# ActiveHeadphone2.net
KiCad netlist of a schematic drawn in EAGLE
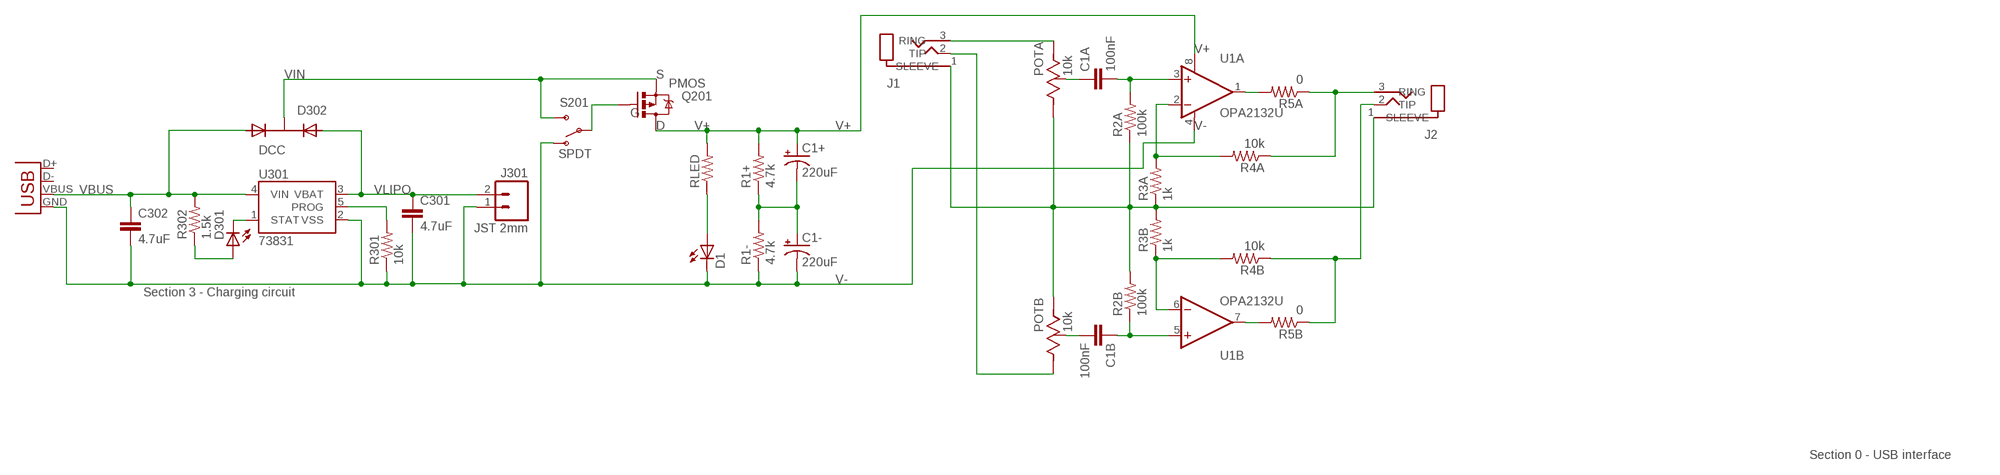
[diagram p0: schematic, sheet 1]

(export (version "E")
  (design (tool "Eeschema 10.0.6"))
  (components
    (comp (ref "C1+")
      (value "220uF")
      (footprint "eagle-import:EIA7343")
      (libsource (lib "eagle-import") (part "CAP_POL7343"))
    )
    (comp (ref "C1-")
      (value "220uF")
      (footprint "eagle-import:EIA7343")
      (libsource (lib "eagle-import") (part "CAP_POL7343"))
    )
    (comp (ref "C1A")
      (value "100nF")
      (footprint "eagle-import:0603-CAP")
      (libsource (lib "eagle-import") (part "CAP0603-CAP"))
    )
    (comp (ref "C1B")
      (value "100nF")
      (footprint "eagle-import:0603-CAP")
      (libsource (lib "eagle-import") (part "CAP0603-CAP"))
    )
    (comp (ref "C301")
      (value "4.7uF")
      (footprint "eagle-import:0603-CAP")
      (libsource (lib "eagle-import") (part "CAP0603-CAP"))
    )
    (comp (ref "C302")
      (value "4.7uF")
      (footprint "eagle-import:0603-CAP")
      (libsource (lib "eagle-import") (part "CAP0603-CAP"))
    )
    (comp (ref "D1")
      (value "RED")
      (footprint "eagle-import:LED-0603")
      (libsource (lib "eagle-import") (part "LED0603"))
    )
    (comp (ref "D301")
      (value "RED")
      (footprint "eagle-import:LED-0603")
      (libsource (lib "eagle-import") (part "LED0603"))
    )
    (comp (ref "D302")
      (value "DCC")
      (footprint "eagle-import:SOT-23-3")
      (libsource (lib "eagle-import") (part "PMEG2005CT"))
    )
    (comp (ref "J1")
      (value "3.5mm")
      (footprint "eagle-import:SJ1-3513-SMT")
      (libsource (lib "eagle-import") (part "SJ1-3513-SMT"))
    )
    (comp (ref "J2")
      (value "3.5mm")
      (footprint "eagle-import:SJ1-3513-SMT")
      (libsource (lib "eagle-import") (part "SJ1-3513-SMT"))
    )
    (comp (ref "J003")
      (value "USBSMD")
      (footprint "eagle-import:USB-MINIB")
      (libsource (lib "eagle-import") (part "USBSMD"))
    )
    (comp (ref "J301")
      (value "JST 2mm")
      (footprint "eagle-import:JST-2-SMD")
      (libsource (lib "eagle-import") (part "M02-JST-2MM-SMT"))
    )
    (comp (ref "POTA")
      (value "10k")
      (footprint "eagle-import:3352T")
      (libsource (lib "eagle-import") (part "3352T"))
    )
    (comp (ref "POTB")
      (value "10k")
      (footprint "eagle-import:3352T")
      (libsource (lib "eagle-import") (part "3352T"))
    )
    (comp (ref "Q201")
      (value "PMOS")
      (footprint "eagle-import:SOT23-3")
      (libsource (lib "eagle-import") (part "MOSFET-PCHANNELSMD"))
    )
    (comp (ref "R1+")
      (value "4.7k")
      (footprint "eagle-import:0603-RES")
      (libsource (lib "eagle-import") (part "RESISTOR0603-RES"))
    )
    (comp (ref "R1-")
      (value "4.7k")
      (footprint "eagle-import:0603-RES")
      (libsource (lib "eagle-import") (part "RESISTOR0603-RES"))
    )
    (comp (ref "R2A")
      (value "100k")
      (footprint "eagle-import:0603-RES")
      (libsource (lib "eagle-import") (part "RESISTOR0603-RES"))
    )
    (comp (ref "R2B")
      (value "100k")
      (footprint "eagle-import:0603-RES")
      (libsource (lib "eagle-import") (part "RESISTOR0603-RES"))
    )
    (comp (ref "R3A")
      (value "1k")
      (footprint "eagle-import:0603-RES")
      (libsource (lib "eagle-import") (part "RESISTOR0603-RES"))
    )
    (comp (ref "R3B")
      (value "1k")
      (footprint "eagle-import:0603-RES")
      (libsource (lib "eagle-import") (part "RESISTOR0603-RES"))
    )
    (comp (ref "R4A")
      (value "10k")
      (footprint "eagle-import:0603-RES")
      (libsource (lib "eagle-import") (part "RESISTOR0603-RES"))
    )
    (comp (ref "R4B")
      (value "10k")
      (footprint "eagle-import:0603-RES")
      (libsource (lib "eagle-import") (part "RESISTOR0603-RES"))
    )
    (comp (ref "R5A")
      (value "0")
      (footprint "eagle-import:0603-RES")
      (libsource (lib "eagle-import") (part "RESISTOR0603-RES"))
    )
    (comp (ref "R5B")
      (value "0")
      (footprint "eagle-import:0603-RES")
      (libsource (lib "eagle-import") (part "RESISTOR0603-RES"))
    )
    (comp (ref "R301")
      (value "10k")
      (footprint "eagle-import:0603-RES")
      (libsource (lib "eagle-import") (part "RESISTOR0603-RES"))
    )
    (comp (ref "R302")
      (value "1.5k")
      (footprint "eagle-import:0603-RES")
      (libsource (lib "eagle-import") (part "RESISTOR0603-RES"))
    )
    (comp (ref "RLED")
      (value "RESISTOR0603-RES")
      (footprint "eagle-import:0603-RES")
      (libsource (lib "eagle-import") (part "RESISTOR0603-RES"))
    )
    (comp (ref "S201")
      (value "SPDT")
      (footprint "eagle-import:AYZ0202")
      (libsource (lib "eagle-import") (part "SWITCH-SPSTSMD"))
    )
    (comp (ref "U1")
      (value "OPA2132U")
      (footprint "eagle-import:SO08")
      (fields (field (name "MF") "TEXAS INSTRUMENTS"))
      (libsource (lib "eagle-import") (part "OPA2132U"))
    )
    (comp (ref "U301")
      (value "73831")
      (footprint "eagle-import:SOT23-5")
      (libsource (lib "eagle-import") (part "MCP73831"))
    )
  )
  (nets
    (net (code "1") (name "/V+") (class "Default")
      (node (ref "C1+") (pin "A") (pinfunction "+_A") (pintype "passive"))
      (node (ref "Q201") (pin "3") (pinfunction "D_3") (pintype "passive"))
      (node (ref "R1+") (pin "2") (pinfunction "2_2") (pintype "passive"))
      (node (ref "RLED") (pin "2") (pinfunction "2_2") (pintype "passive"))
      (node (ref "U1") (pin "8") (pinfunction "V+_8") (pintype "power_in"))
    )
    (net (code "2") (name "/V-") (class "Default")
      (node (ref "C1-") (pin "C") (pinfunction "-_C") (pintype "passive"))
      (node (ref "C301") (pin "2") (pinfunction "2_2") (pintype "passive"))
      (node (ref "C302") (pin "2") (pinfunction "2_2") (pintype "passive"))
      (node (ref "D1") (pin "C") (pinfunction "C_C") (pintype "passive"))
      (node (ref "J003") (pin "GND") (pinfunction "GND_GND") (pintype "bidirectional"))
      (node (ref "J301") (pin "1") (pinfunction "1_1") (pintype "passive"))
      (node (ref "R1-") (pin "1") (pinfunction "1_1") (pintype "passive"))
      (node (ref "R301") (pin "1") (pinfunction "1_1") (pintype "passive"))
      (node (ref "S201") (pin "1") (pinfunction "O_1") (pintype "passive"))
      (node (ref "U1") (pin "4") (pinfunction "V-_4") (pintype "power_in"))
      (node (ref "U301") (pin "2") (pinfunction "VSS_2") (pintype "power_in"))
    )
    (net (code "3") (name "/VBUS") (class "Default")
      (node (ref "C302") (pin "1") (pinfunction "1_1") (pintype "passive"))
      (node (ref "D302") (pin "1") (pinfunction "A1_1") (pintype "passive"))
      (node (ref "J003") (pin "VBUS") (pinfunction "VBUS_VBUS") (pintype "bidirectional"))
      (node (ref "R302") (pin "2") (pinfunction "2_2") (pintype "passive"))
      (node (ref "U301") (pin "4") (pinfunction "VIN_4") (pintype "power_in"))
    )
    (net (code "4") (name "/VIN") (class "Default")
      (node (ref "D302") (pin "3") (pinfunction "K_3") (pintype "passive"))
      (node (ref "Q201") (pin "2") (pinfunction "S_2") (pintype "passive"))
      (node (ref "S201") (pin "3") (pinfunction "S_3") (pintype "passive"))
    )
    (net (code "5") (name "/VLIPO") (class "Default")
      (node (ref "C301") (pin "1") (pinfunction "1_1") (pintype "passive"))
      (node (ref "D302") (pin "2") (pinfunction "A2_2") (pintype "passive"))
      (node (ref "J301") (pin "2") (pinfunction "2_2") (pintype "passive"))
      (node (ref "U301") (pin "3") (pinfunction "VBAT_3") (pintype "power_in"))
    )
    (net (code "6") (name "Net-(C1+--)") (class "Default")
      (node (ref "C1+") (pin "C") (pinfunction "-_C") (pintype "passive"))
      (node (ref "C1-") (pin "A") (pinfunction "+_A") (pintype "passive"))
      (node (ref "R1+") (pin "1") (pinfunction "1_1") (pintype "passive"))
      (node (ref "R1-") (pin "2") (pinfunction "2_2") (pintype "passive"))
    )
    (net (code "7") (name "Net-(D1-PadA)") (class "Default")
      (node (ref "D1") (pin "A") (pinfunction "A_A") (pintype "passive"))
      (node (ref "RLED") (pin "1") (pinfunction "1_1") (pintype "passive"))
    )
    (net (code "8") (name "Net-(D301-PadA)") (class "Default")
      (node (ref "D301") (pin "A") (pinfunction "A_A") (pintype "passive"))
      (node (ref "R302") (pin "1") (pinfunction "1_1") (pintype "passive"))
    )
    (net (code "9") (name "Net-(J1-RING)") (class "Default")
      (node (ref "J1") (pin "3") (pinfunction "RING_3") (pintype "bidirectional"))
      (node (ref "POTA") (pin "3") (pinfunction "CW_3") (pintype "bidirectional"))
    )
    (net (code "10") (name "Net-(J1-SLEEVE)") (class "Default")
      (node (ref "J1") (pin "1") (pinfunction "SLEEVE_1") (pintype "bidirectional"))
      (node (ref "J2") (pin "1") (pinfunction "SLEEVE_1") (pintype "bidirectional"))
      (node (ref "POTA") (pin "1") (pinfunction "CCW_1") (pintype "bidirectional"))
      (node (ref "POTB") (pin "3") (pinfunction "CW_3") (pintype "bidirectional"))
      (node (ref "R2A") (pin "1") (pinfunction "1_1") (pintype "passive"))
      (node (ref "R2B") (pin "2") (pinfunction "2_2") (pintype "passive"))
      (node (ref "R3A") (pin "1") (pinfunction "1_1") (pintype "passive"))
      (node (ref "R3B") (pin "2") (pinfunction "2_2") (pintype "passive"))
    )
    (net (code "11") (name "Net-(J1-TIP)") (class "Default")
      (node (ref "J1") (pin "2") (pinfunction "TIP_2") (pintype "bidirectional"))
      (node (ref "POTB") (pin "1") (pinfunction "CCW_1") (pintype "bidirectional"))
    )
    (net (code "12") (name "Net-(J2-RING)") (class "Default")
      (node (ref "J2") (pin "3") (pinfunction "RING_3") (pintype "bidirectional"))
      (node (ref "R4A") (pin "1") (pinfunction "1_1") (pintype "passive"))
      (node (ref "R5A") (pin "1") (pinfunction "1_1") (pintype "passive"))
    )
    (net (code "13") (name "Net-(J2-TIP)") (class "Default")
      (node (ref "J2") (pin "2") (pinfunction "TIP_2") (pintype "bidirectional"))
      (node (ref "R4B") (pin "1") (pinfunction "1_1") (pintype "passive"))
      (node (ref "R5B") (pin "1") (pinfunction "1_1") (pintype "passive"))
    )
    (net (code "14") (name "Net-(POTA-WIPER)") (class "Default")
      (node (ref "C1A") (pin "1") (pinfunction "1_1") (pintype "passive"))
      (node (ref "POTA") (pin "2") (pinfunction "WIPER_2") (pintype "bidirectional"))
    )
    (net (code "15") (name "Net-(POTB-WIPER)") (class "Default")
      (node (ref "C1B") (pin "2") (pinfunction "2_2") (pintype "passive"))
      (node (ref "POTB") (pin "2") (pinfunction "WIPER_2") (pintype "bidirectional"))
    )
    (net (code "16") (name "Net-(Q201-G)") (class "Default")
      (node (ref "Q201") (pin "1") (pinfunction "G_1") (pintype "passive"))
      (node (ref "S201") (pin "2") (pinfunction "P_2") (pintype "passive"))
    )
    (net (code "17") (name "Net-(U1A-+IN)") (class "Default")
      (node (ref "C1A") (pin "2") (pinfunction "2_2") (pintype "passive"))
      (node (ref "R2A") (pin "2") (pinfunction "2_2") (pintype "passive"))
      (node (ref "U1") (pin "3") (pinfunction "+IN_3") (pintype "input"))
    )
    (net (code "18") (name "Net-(U1A--IN)") (class "Default")
      (node (ref "R3A") (pin "2") (pinfunction "2_2") (pintype "passive"))
      (node (ref "R4A") (pin "2") (pinfunction "2_2") (pintype "passive"))
      (node (ref "U1") (pin "2") (pinfunction "-IN_2") (pintype "input"))
    )
    (net (code "19") (name "Net-(U1A-OUT)") (class "Default")
      (node (ref "R5A") (pin "2") (pinfunction "2_2") (pintype "passive"))
      (node (ref "U1") (pin "1") (pinfunction "OUT_1") (pintype "output"))
    )
    (net (code "20") (name "Net-(U1B-+IN)") (class "Default")
      (node (ref "C1B") (pin "1") (pinfunction "1_1") (pintype "passive"))
      (node (ref "R2B") (pin "1") (pinfunction "1_1") (pintype "passive"))
      (node (ref "U1") (pin "5") (pinfunction "+IN_5") (pintype "input"))
    )
    (net (code "21") (name "Net-(U1B--IN)") (class "Default")
      (node (ref "R3B") (pin "1") (pinfunction "1_1") (pintype "passive"))
      (node (ref "R4B") (pin "2") (pinfunction "2_2") (pintype "passive"))
      (node (ref "U1") (pin "6") (pinfunction "-IN_6") (pintype "input"))
    )
    (net (code "22") (name "Net-(U1B-OUT)") (class "Default")
      (node (ref "R5B") (pin "2") (pinfunction "2_2") (pintype "passive"))
      (node (ref "U1") (pin "7") (pinfunction "OUT_7") (pintype "output"))
    )
    (net (code "23") (name "Net-(U301-PROG)") (class "Default")
      (node (ref "R301") (pin "2") (pinfunction "2_2") (pintype "passive"))
      (node (ref "U301") (pin "5") (pinfunction "PROG_5") (pintype "input"))
    )
    (net (code "24") (name "Net-(U301-STAT)") (class "Default")
      (node (ref "D301") (pin "C") (pinfunction "C_C") (pintype "passive"))
      (node (ref "U301") (pin "1") (pinfunction "STAT_1") (pintype "output"))
    )
    (net (code "25") (name "unconnected-(J003-PadD+)") (class "Default")
      (node (ref "J003") (pin "D+") (pinfunction "D+_D+") (pintype "bidirectional"))
    )
    (net (code "26") (name "unconnected-(J003-PadD-)") (class "Default")
      (node (ref "J003") (pin "D-") (pinfunction "D-_D-") (pintype "bidirectional"))
    )
  )
)
